# STML451RE_Buck.net
KiCad netlist of a schematic drawn in EAGLE
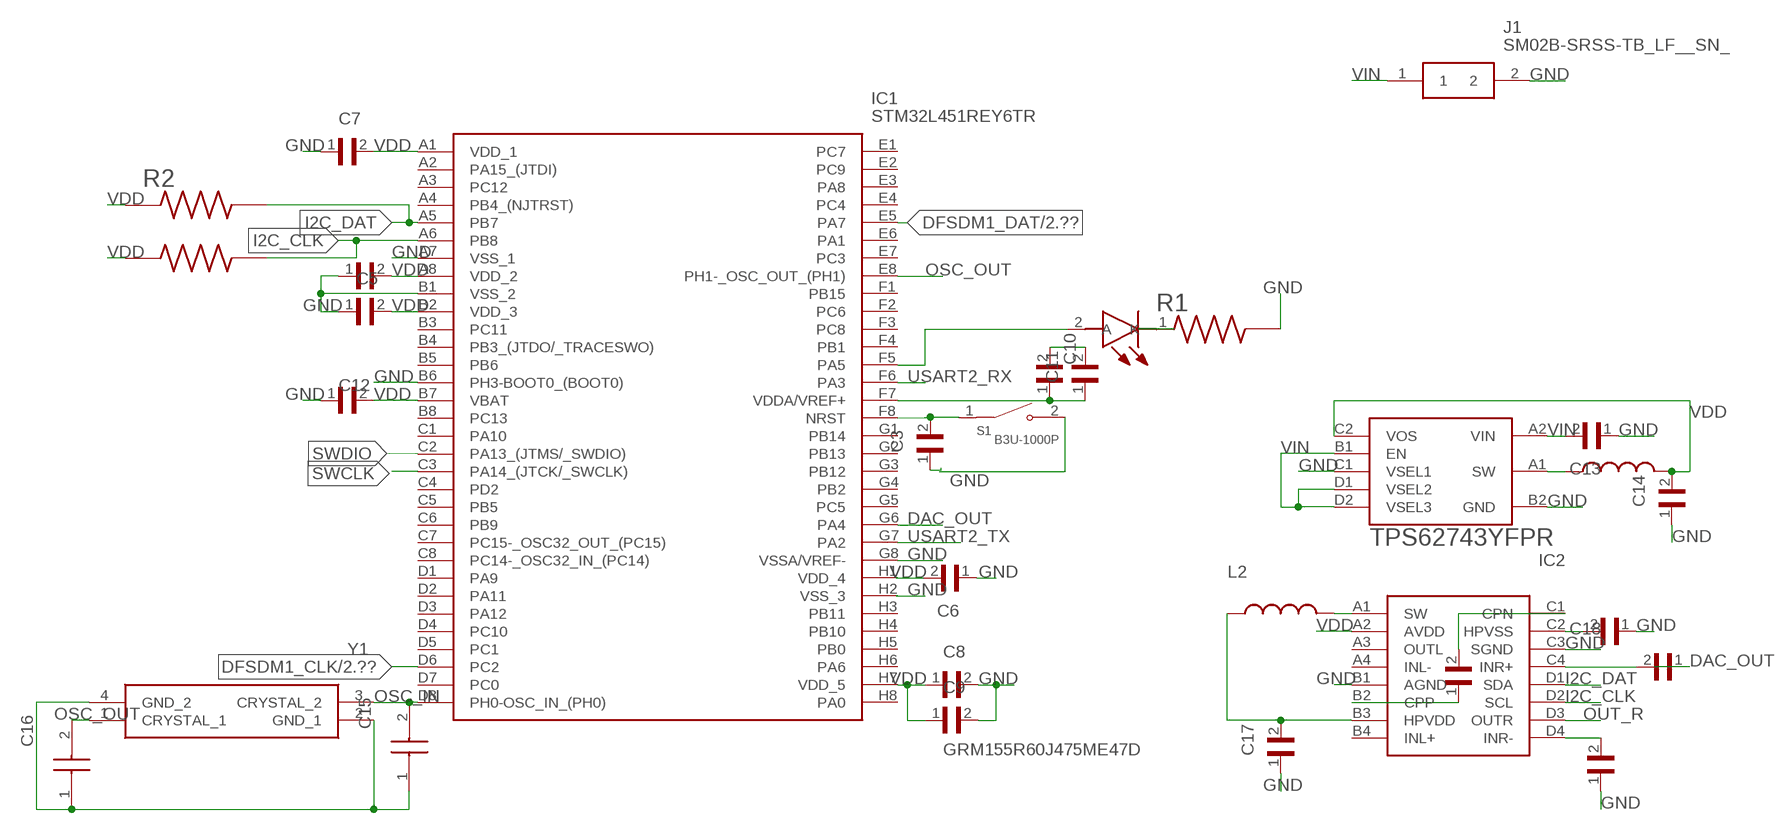
[diagram p0: schematic, sheet 1]
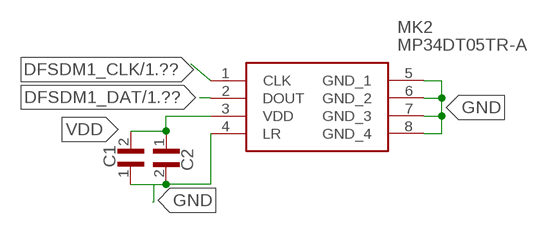
[diagram p1: schematic, sheet 2]

(export (version "E")
  (design (tool "Eeschema 10.0.6"))
  (components
    (comp (ref "C1")
      (value "GRM033C80J104KE15D")
      (footprint "eagle-import:CAPC0603X33N")
      (fields (field (name "DIGI-KEY_PART_NUMBER") "490-10390-1-ND") (field (name "MF") "Murata Electronics"))
      (libsource (lib "eagle-import") (part "GRM033C80J104KE15D"))
    )
    (comp (ref "C2")
      (value "JMK105C6105KV-F")
      (footprint "eagle-import:CAPC1005X55N")
      (fields (field (name "DIGI-KEY_PART_NUMBER") "587-3381-1-ND") (field (name "MF") "Taiyo Yuden"))
      (libsource (lib "eagle-import") (part "JMK105C6105KV-F"))
    )
    (comp (ref "MK2")
      (value "MP34DT05TR-A")
      (footprint "eagle-import:MP34DT05TRA")
      (fields (field (name "MOUSER_PART_NUMBER") "511-MP34DT05TR-A"))
      (libsource (lib "eagle-import") (part "MP34DT05TR-A"))
    )
    (comp (ref "C3")
      (value "GRM033C80J104KE15D")
      (footprint "eagle-import:CAPC0603X33N")
      (fields (field (name "DIGI-KEY_PART_NUMBER") "490-10390-1-ND") (field (name "MF") "Murata Electronics"))
      (libsource (lib "eagle-import") (part "GRM033C80J104KE15D"))
    )
    (comp (ref "C4")
      (value "GRM033C80J104KE15D")
      (footprint "eagle-import:CAPC0603X33N")
      (fields (field (name "DIGI-KEY_PART_NUMBER") "490-10390-1-ND") (field (name "MF") "Murata Electronics"))
      (libsource (lib "eagle-import") (part "GRM033C80J104KE15D"))
    )
    (comp (ref "C5")
      (value "GRM033C80J104KE15D")
      (footprint "eagle-import:CAPC0603X33N")
      (fields (field (name "DIGI-KEY_PART_NUMBER") "490-10390-1-ND") (field (name "MF") "Murata Electronics"))
      (libsource (lib "eagle-import") (part "GRM033C80J104KE15D"))
    )
    (comp (ref "C6")
      (value "GRM033C80J104KE15D")
      (footprint "eagle-import:CAPC0603X33N")
      (fields (field (name "DIGI-KEY_PART_NUMBER") "490-10390-1-ND") (field (name "MF") "Murata Electronics"))
      (libsource (lib "eagle-import") (part "GRM033C80J104KE15D"))
    )
    (comp (ref "C7")
      (value "GRM033C80J104KE15D")
      (footprint "eagle-import:CAPC0603X33N")
      (fields (field (name "DIGI-KEY_PART_NUMBER") "490-10390-1-ND") (field (name "MF") "Murata Electronics"))
      (libsource (lib "eagle-import") (part "GRM033C80J104KE15D"))
    )
    (comp (ref "C8")
      (value "GRM033C80J104KE15D")
      (footprint "eagle-import:CAPC0603X33N")
      (fields (field (name "DIGI-KEY_PART_NUMBER") "490-10390-1-ND") (field (name "MF") "Murata Electronics"))
      (libsource (lib "eagle-import") (part "GRM033C80J104KE15D"))
    )
    (comp (ref "C9")
      (value "GRM155R60J475ME47D")
      (footprint "eagle-import:CAPC1005X60N")
      (fields (field (name "DIGI-KEY_PART_NUMBER") "490-5915-1-ND") (field (name "MF") "Murata"))
      (libsource (lib "eagle-import") (part "GRM155R60J475ME47D"))
    )
    (comp (ref "C10")
      (value "GRM033C80J104KE15D")
      (footprint "eagle-import:CAPC0603X33N")
      (fields (field (name "DIGI-KEY_PART_NUMBER") "490-10390-1-ND") (field (name "MF") "Murata Electronics"))
      (libsource (lib "eagle-import") (part "GRM033C80J104KE15D"))
    )
    (comp (ref "C11")
      (value "JMK105C6105KV-F")
      (footprint "eagle-import:CAPC1005X55N")
      (fields (field (name "DIGI-KEY_PART_NUMBER") "587-3381-1-ND") (field (name "MF") "Taiyo Yuden"))
      (libsource (lib "eagle-import") (part "JMK105C6105KV-F"))
    )
    (comp (ref "C12")
      (value "GRM033C80J104KE15D")
      (footprint "eagle-import:CAPC0603X33N")
      (fields (field (name "DIGI-KEY_PART_NUMBER") "490-10390-1-ND") (field (name "MF") "Murata Electronics"))
      (libsource (lib "eagle-import") (part "GRM033C80J104KE15D"))
    )
    (comp (ref "C13")
      (value "GRM155R60J475ME47D")
      (footprint "eagle-import:CAPC1005X60N")
      (fields (field (name "DIGI-KEY_PART_NUMBER") "490-5915-1-ND") (field (name "MF") "Murata"))
      (libsource (lib "eagle-import") (part "GRM155R60J475ME47D"))
    )
    (comp (ref "C14")
      (value "GRM155R60J106ME15D")
      (footprint "eagle-import:CAPC1005X65N")
      (fields (field (name "DIGI-KEY_PART_NUMBER") "490-13238-1-ND") (field (name "MF") "Murata"))
      (libsource (lib "eagle-import") (part "GRM155R60J106ME15D"))
    )
    (comp (ref "C15")
      (value "0101YA120JAT2A")
      (footprint "eagle-import:CAPC0402X22N")
      (fields (field (name "MOUSER_PART_NUMBER") "581-0101YA120JAT2A"))
      (libsource (lib "eagle-import") (part "0101YA120JAT2A"))
    )
    (comp (ref "C16")
      (value "0101YA120JAT2A")
      (footprint "eagle-import:CAPC0402X22N")
      (fields (field (name "MOUSER_PART_NUMBER") "581-0101YA120JAT2A"))
      (libsource (lib "eagle-import") (part "0101YA120JAT2A"))
    )
    (comp (ref "C17")
      (value "GRM155R60J225KE95D")
      (footprint "eagle-import:CAPC1005X55N")
      (fields (field (name "DIGI-KEY_PART_NUMBER") "490-12532-1-ND") (field (name "MF") "Murata"))
      (libsource (lib "eagle-import") (part "GRM155R60J225KE95D"))
    )
    (comp (ref "C18")
      (value "GRM155R60J225KE95D")
      (footprint "eagle-import:CAPC1005X55N")
      (fields (field (name "DIGI-KEY_PART_NUMBER") "490-12532-1-ND") (field (name "MF") "Murata"))
      (libsource (lib "eagle-import") (part "GRM155R60J225KE95D"))
    )
    (comp (ref "C19")
      (value "JMK105C6105KV-F")
      (footprint "eagle-import:CAPC1005X55N")
      (fields (field (name "DIGI-KEY_PART_NUMBER") "587-3381-1-ND") (field (name "MF") "Taiyo Yuden"))
      (libsource (lib "eagle-import") (part "JMK105C6105KV-F"))
    )
    (comp (ref "C20")
      (value "JMK105C6105KV-F")
      (footprint "eagle-import:CAPC1005X55N")
      (fields (field (name "DIGI-KEY_PART_NUMBER") "587-3381-1-ND") (field (name "MF") "Taiyo Yuden"))
      (libsource (lib "eagle-import") (part "JMK105C6105KV-F"))
    )
    (comp (ref "C21")
      (value "JMK105C6105KV-F")
      (footprint "eagle-import:CAPC1005X55N")
      (fields (field (name "DIGI-KEY_PART_NUMBER") "587-3381-1-ND") (field (name "MF") "Taiyo Yuden"))
      (libsource (lib "eagle-import") (part "JMK105C6105KV-F"))
    )
    (comp (ref "IC1")
      (value "STM32L451REY6TR")
      (footprint "eagle-import:BGA64C40P8X8_336X366X58")
      (fields (field (name "MOUSER_PART_NUMBER") "511-STM32L451REY6TR"))
      (libsource (lib "eagle-import") (part "STM32L451REY6TR"))
    )
    (comp (ref "IC2")
      (value "TPA6140A2YFFT")
      (footprint "eagle-import:BGA16C40P4X4_156X156X63")
      (fields (field (name "MOUSER_PART_NUMBER") "595-TPA6140A2YFFT"))
      (libsource (lib "eagle-import") (part "TPA6140A2YFFT"))
    )
    (comp (ref "J1")
      (value "SM02B-SRSS-TB_LF__SN_")
      (footprint "eagle-import:SM02B-SRSS-TB")
      (fields (field (name "ARROW_PART_NUMBER") "SM02B-SRSS-TB(LF)(SN)"))
      (libsource (lib "eagle-import") (part "SM02B-SRSS-TB_LF__SN_"))
    )
    (comp (ref "L1")
      (value "1285AS-H-2R2M=P2")
      (footprint "eagle-import:INDC2016X100N")
      (fields (field (name "DIGI-KEY_PART_NUMBER") "490-10600-1-ND") (field (name "MF") "Murata Electronics"))
      (libsource (lib "eagle-import") (part "1285AS-H-2R2M=P2"))
    )
    (comp (ref "L2")
      (value "LQM21PN2R2MC0D")
      (footprint "eagle-import:INDC2012X55N")
      (fields (field (name "DIGI-KEY_PART_NUMBER") "490-4994-1-ND") (field (name "MF") "Murata"))
      (libsource (lib "eagle-import") (part "LQM21PN2R2MC0D"))
    )
    (comp (ref "LED1")
      (value "VLMS1500-GS08")
      (footprint "eagle-import:VLMG1500GS08")
      (fields (field (name "MOUSER_PART_NUMBER") "78-VLMS1500-GS08"))
      (libsource (lib "eagle-import") (part "VLMS1500-GS08"))
    )
    (comp (ref "R1")
      (value "CRCW02012K20FKED")
      (footprint "eagle-import:RESC0603X28N")
      (fields (field (name "DIGI-KEY_PART_NUMBER") "541-2.20KAABCT-ND") (field (name "MF") "Vishay"))
      (libsource (lib "eagle-import") (part "CRCW02012K20FKED"))
    )
    (comp (ref "R2")
      (value "ERA-2AEB122X")
      (footprint "eagle-import:RESC1005X40N")
      (fields (field (name "DIGI-KEY_PART_NUMBER") "P1.2KDCCT-ND") (field (name "MF") "Panasonic"))
      (libsource (lib "eagle-import") (part "ERA-2AEB122X"))
    )
    (comp (ref "R3")
      (value "ERA-2AEB122X")
      (footprint "eagle-import:RESC1005X40N")
      (fields (field (name "DIGI-KEY_PART_NUMBER") "P1.2KDCCT-ND") (field (name "MF") "Panasonic"))
      (libsource (lib "eagle-import") (part "ERA-2AEB122X"))
    )
    (comp (ref "S1")
      (value "B3U-1000P")
      (footprint "eagle-import:SW_B3U-1000P")
      (fields (field (name "DIGI-KEY_PART_NUMBER") "SW1020CT-ND") (field (name "MF") "Omron"))
      (libsource (lib "eagle-import") (part "B3U-1000P"))
    )
    (comp (ref "U1")
      (value "TPS62743YFPR")
      (footprint "eagle-import:BGA8N40P2X4_87X156X50")
      (fields (field (name "DIGI-KEY_PART_NUMBER") "296-42392-1-ND") (field (name "MF") "Texas Instruments"))
      (libsource (lib "eagle-import") (part "TPS62743YFPR"))
    )
    (comp (ref "Y1")
      (value "FL0800008Q")
      (footprint "eagle-import:FL0800008Q")
      (fields (field (name "MOUSER_PART_NUMBER") "729-FL0800008Q"))
      (libsource (lib "eagle-import") (part "FL0800008Q"))
    )
  )
  (nets
    (net (code "1") (name "DAC_OUT") (class "Default")
      (node (ref "C21") (pin "1") (pinfunction "1_1") (pintype "passive"))
      (node (ref "IC1") (pin "G6") (pinfunction "PA4_G6") (pintype "bidirectional"))
    )
    (net (code "2") (name "DFSDM1_CLK") (class "Default")
      (node (ref "IC1") (pin "D6") (pinfunction "PC2_D6") (pintype "bidirectional"))
      (node (ref "MK2") (pin "1") (pinfunction "CLK_1") (pintype "bidirectional"))
    )
    (net (code "3") (name "DFSDM1_DAT") (class "Default")
      (node (ref "IC1") (pin "E5") (pinfunction "PA7_E5") (pintype "bidirectional"))
      (node (ref "MK2") (pin "2") (pinfunction "DOUT_2") (pintype "bidirectional"))
    )
    (net (code "4") (name "GND") (class "Default")
      (node (ref "C12") (pin "1") (pinfunction "1_1") (pintype "passive"))
      (node (ref "C13") (pin "1") (pinfunction "1_1") (pintype "passive"))
      (node (ref "C14") (pin "1") (pinfunction "1_1") (pintype "passive"))
      (node (ref "C15") (pin "1") (pinfunction "1_1") (pintype "bidirectional"))
      (node (ref "C16") (pin "1") (pinfunction "1_1") (pintype "bidirectional"))
      (node (ref "C17") (pin "1") (pinfunction "1_1") (pintype "passive"))
      (node (ref "C18") (pin "1") (pinfunction "1_1") (pintype "passive"))
      (node (ref "C20") (pin "1") (pinfunction "1_1") (pintype "passive"))
      (node (ref "C3") (pin "1") (pinfunction "1_1") (pintype "passive"))
      (node (ref "C4") (pin "1") (pinfunction "1_1") (pintype "passive"))
      (node (ref "C5") (pin "1") (pinfunction "1_1") (pintype "passive"))
      (node (ref "C6") (pin "1") (pinfunction "1_1") (pintype "passive"))
      (node (ref "C7") (pin "1") (pinfunction "1_1") (pintype "passive"))
      (node (ref "C8") (pin "2") (pinfunction "2_2") (pintype "passive"))
      (node (ref "C9") (pin "2") (pinfunction "2_2") (pintype "passive"))
      (node (ref "IC1") (pin "A7") (pinfunction "VSS_1_A7") (pintype "bidirectional"))
      (node (ref "IC1") (pin "B1") (pinfunction "VSS_2_B1") (pintype "bidirectional"))
      (node (ref "IC1") (pin "B6") (pinfunction "PH3-BOOT0_(BOOT0)_B6") (pintype "bidirectional"))
      (node (ref "IC1") (pin "G8") (pinfunction "VSSA/VREF-_G8") (pintype "bidirectional"))
      (node (ref "IC1") (pin "H2") (pinfunction "VSS_3_H2") (pintype "bidirectional"))
      (node (ref "IC2") (pin "B1") (pinfunction "AGND_B1") (pintype "bidirectional"))
      (node (ref "IC2") (pin "C3") (pinfunction "SGND_C3") (pintype "bidirectional"))
      (node (ref "J1") (pin "2") (pinfunction "2_2") (pintype "bidirectional"))
      (node (ref "MK2") (pin "5") (pinfunction "GND_1_5") (pintype "bidirectional"))
      (node (ref "MK2") (pin "6") (pinfunction "GND_2_6") (pintype "bidirectional"))
      (node (ref "MK2") (pin "7") (pinfunction "GND_3_7") (pintype "bidirectional"))
      (node (ref "MK2") (pin "8") (pinfunction "GND_4_8") (pintype "bidirectional"))
      (node (ref "R1") (pin "2") (pinfunction "2_2") (pintype "passive"))
      (node (ref "U1") (pin "B2") (pinfunction "GND_B2") (pintype "passive"))
      (node (ref "U1") (pin "C1") (pinfunction "VSEL1_C1") (pintype "input"))
      (node (ref "Y1") (pin "2") (pinfunction "GND_1_2") (pintype "bidirectional"))
      (node (ref "Y1") (pin "4") (pinfunction "GND_2_4") (pintype "bidirectional"))
    )
    (net (code "5") (name "I2C_CLK") (class "Default")
      (node (ref "IC1") (pin "A6") (pinfunction "PB8_A6") (pintype "bidirectional"))
      (node (ref "IC2") (pin "D2") (pinfunction "SCL_D2") (pintype "bidirectional"))
      (node (ref "R3") (pin "2") (pinfunction "2_2") (pintype "passive"))
    )
    (net (code "6") (name "I2C_DAT") (class "Default")
      (node (ref "IC1") (pin "A5") (pinfunction "PB7_A5") (pintype "bidirectional"))
      (node (ref "IC2") (pin "D1") (pinfunction "SDA_D1") (pintype "bidirectional"))
      (node (ref "R2") (pin "2") (pinfunction "2_2") (pintype "passive"))
    )
    (net (code "7") (name "Net-(C3-Pad2)") (class "Default")
      (node (ref "C3") (pin "2") (pinfunction "2_2") (pintype "passive"))
      (node (ref "S1") (pin "1") (pinfunction "1_1") (pintype "passive"))
    )
    (net (code "8") (name "Net-(C10-Pad2)") (class "Default")
      (node (ref "C10") (pin "2") (pinfunction "2_2") (pintype "passive"))
      (node (ref "C11") (pin "2") (pinfunction "2_2") (pintype "passive"))
    )
    (net (code "9") (name "Net-(IC1-PA5)") (class "Default")
      (node (ref "IC1") (pin "F5") (pinfunction "PA5_F5") (pintype "bidirectional"))
      (node (ref "LED1") (pin "2") (pinfunction "A_2") (pintype "bidirectional"))
    )
    (net (code "10") (name "Net-(IC1-VDDA{slash}VREF+)") (class "Default")
      (node (ref "C10") (pin "1") (pinfunction "1_1") (pintype "passive"))
      (node (ref "C11") (pin "1") (pinfunction "1_1") (pintype "passive"))
      (node (ref "IC1") (pin "F7") (pinfunction "VDDA/VREF+_F7") (pintype "bidirectional"))
    )
    (net (code "11") (name "Net-(IC2-CPN)") (class "Default")
      (node (ref "C19") (pin "2") (pinfunction "2_2") (pintype "passive"))
      (node (ref "IC2") (pin "C1") (pinfunction "CPN_C1") (pintype "bidirectional"))
    )
    (net (code "12") (name "Net-(IC2-CPP)") (class "Default")
      (node (ref "C19") (pin "1") (pinfunction "1_1") (pintype "passive"))
      (node (ref "IC2") (pin "B2") (pinfunction "CPP_B2") (pintype "bidirectional"))
    )
    (net (code "13") (name "Net-(IC2-HPVDD)") (class "Default")
      (node (ref "C17") (pin "2") (pinfunction "2_2") (pintype "passive"))
      (node (ref "IC2") (pin "B3") (pinfunction "HPVDD_B3") (pintype "bidirectional"))
      (node (ref "L2") (pin "1") (pinfunction "1_1") (pintype "passive"))
    )
    (net (code "14") (name "Net-(IC2-HPVSS)") (class "Default")
      (node (ref "C18") (pin "2") (pinfunction "2_2") (pintype "passive"))
      (node (ref "IC2") (pin "C2") (pinfunction "HPVSS_C2") (pintype "bidirectional"))
    )
    (net (code "15") (name "Net-(IC2-INR+)") (class "Default")
      (node (ref "C21") (pin "2") (pinfunction "2_2") (pintype "passive"))
      (node (ref "IC2") (pin "C4") (pinfunction "INR+_C4") (pintype "bidirectional"))
    )
    (net (code "16") (name "Net-(IC2-INR-)") (class "Default")
      (node (ref "C20") (pin "2") (pinfunction "2_2") (pintype "passive"))
      (node (ref "IC2") (pin "D4") (pinfunction "INR-_D4") (pintype "bidirectional"))
    )
    (net (code "17") (name "Net-(IC2-SW)") (class "Default")
      (node (ref "IC2") (pin "A1") (pinfunction "SW_A1") (pintype "bidirectional"))
      (node (ref "L2") (pin "2") (pinfunction "2_2") (pintype "passive"))
    )
    (net (code "18") (name "Net-(LED1-K)") (class "Default")
      (node (ref "LED1") (pin "1") (pinfunction "K_1") (pintype "bidirectional"))
      (node (ref "R1") (pin "1") (pinfunction "1_1") (pintype "passive"))
    )
    (net (code "19") (name "Net-(MK2-LR)") (class "Default")
      (node (ref "C1") (pin "1") (pinfunction "1_1") (pintype "passive"))
      (node (ref "C2") (pin "2") (pinfunction "2_2") (pintype "passive"))
      (node (ref "MK2") (pin "4") (pinfunction "LR_4") (pintype "bidirectional"))
    )
    (net (code "20") (name "Net-(U1-SW)") (class "Default")
      (node (ref "L1") (pin "1") (pinfunction "1_1") (pintype "passive"))
      (node (ref "U1") (pin "A1") (pinfunction "SW_A1") (pintype "output"))
    )
    (net (code "21") (name "OSC_IN") (class "Default")
      (node (ref "C15") (pin "2") (pinfunction "2_2") (pintype "bidirectional"))
      (node (ref "IC1") (pin "D8") (pinfunction "PH0-OSC_IN_(PH0)_D8") (pintype "bidirectional"))
      (node (ref "Y1") (pin "3") (pinfunction "CRYSTAL_2_3") (pintype "bidirectional"))
    )
    (net (code "22") (name "OSC_OUT") (class "Default")
      (node (ref "C16") (pin "2") (pinfunction "2_2") (pintype "bidirectional"))
      (node (ref "IC1") (pin "E8") (pinfunction "PH1-_OSC_OUT_(PH1)_E8") (pintype "bidirectional"))
      (node (ref "Y1") (pin "1") (pinfunction "CRYSTAL_1_1") (pintype "bidirectional"))
    )
    (net (code "23") (name "OUT_R") (class "Default")
      (node (ref "IC2") (pin "D3") (pinfunction "OUTR_D3") (pintype "bidirectional"))
    )
    (net (code "24") (name "SWCLK") (class "Default")
      (node (ref "IC1") (pin "C3") (pinfunction "PA14_(JTCK/_SWCLK)_C3") (pintype "bidirectional"))
    )
    (net (code "25") (name "SWDIO") (class "Default")
      (node (ref "IC1") (pin "C2") (pinfunction "PA13_(JTMS/_SWDIO)_C2") (pintype "bidirectional"))
    )
    (net (code "26") (name "USART2_RX") (class "Default")
      (node (ref "IC1") (pin "F6") (pinfunction "PA3_F6") (pintype "bidirectional"))
    )
    (net (code "27") (name "USART2_TX") (class "Default")
      (node (ref "IC1") (pin "G7") (pinfunction "PA2_G7") (pintype "bidirectional"))
    )
    (net (code "28") (name "VDD") (class "Default")
      (node (ref "C1") (pin "2") (pinfunction "2_2") (pintype "passive"))
      (node (ref "C12") (pin "2") (pinfunction "2_2") (pintype "passive"))
      (node (ref "C14") (pin "2") (pinfunction "2_2") (pintype "passive"))
      (node (ref "C2") (pin "1") (pinfunction "1_1") (pintype "passive"))
      (node (ref "C4") (pin "2") (pinfunction "2_2") (pintype "passive"))
      (node (ref "C5") (pin "2") (pinfunction "2_2") (pintype "passive"))
      (node (ref "C6") (pin "2") (pinfunction "2_2") (pintype "passive"))
      (node (ref "C7") (pin "2") (pinfunction "2_2") (pintype "passive"))
      (node (ref "C8") (pin "1") (pinfunction "1_1") (pintype "passive"))
      (node (ref "C9") (pin "1") (pinfunction "1_1") (pintype "passive"))
      (node (ref "IC1") (pin "A1") (pinfunction "VDD_1_A1") (pintype "bidirectional"))
      (node (ref "IC1") (pin "A8") (pinfunction "VDD_2_A8") (pintype "bidirectional"))
      (node (ref "IC1") (pin "B2") (pinfunction "VDD_3_B2") (pintype "bidirectional"))
      (node (ref "IC1") (pin "B7") (pinfunction "VBAT_B7") (pintype "bidirectional"))
      (node (ref "IC1") (pin "H1") (pinfunction "VDD_4_H1") (pintype "bidirectional"))
      (node (ref "IC1") (pin "H7") (pinfunction "VDD_5_H7") (pintype "bidirectional"))
      (node (ref "IC2") (pin "A2") (pinfunction "AVDD_A2") (pintype "bidirectional"))
      (node (ref "L1") (pin "2") (pinfunction "2_2") (pintype "passive"))
      (node (ref "MK2") (pin "3") (pinfunction "VDD_3") (pintype "bidirectional"))
      (node (ref "R2") (pin "1") (pinfunction "1_1") (pintype "passive"))
      (node (ref "R3") (pin "1") (pinfunction "1_1") (pintype "passive"))
      (node (ref "U1") (pin "C2") (pinfunction "VOS_C2") (pintype "input"))
    )
    (net (code "29") (name "VIN") (class "Default")
      (node (ref "C13") (pin "2") (pinfunction "2_2") (pintype "passive"))
      (node (ref "J1") (pin "1") (pinfunction "1_1") (pintype "bidirectional"))
      (node (ref "U1") (pin "A2") (pinfunction "VIN_A2") (pintype "power_in"))
      (node (ref "U1") (pin "B1") (pinfunction "EN_B1") (pintype "input"))
      (node (ref "U1") (pin "D1") (pinfunction "VSEL2_D1") (pintype "input"))
      (node (ref "U1") (pin "D2") (pinfunction "VSEL3_D2") (pintype "input"))
    )
    (net (code "30") (name "unconnected-(IC1-NRST-PadF8)") (class "Default")
      (node (ref "IC1") (pin "F8") (pinfunction "NRST_F8") (pintype "bidirectional"))
    )
    (net (code "31") (name "unconnected-(IC1-PA0-PadH8)") (class "Default")
      (node (ref "IC1") (pin "H8") (pinfunction "PA0_H8") (pintype "bidirectional"))
    )
    (net (code "32") (name "unconnected-(IC1-PA1-PadE6)") (class "Default")
      (node (ref "IC1") (pin "E6") (pinfunction "PA1_E6") (pintype "bidirectional"))
    )
    (net (code "33") (name "unconnected-(IC1-PA6-PadH6)") (class "Default")
      (node (ref "IC1") (pin "H6") (pinfunction "PA6_H6") (pintype "bidirectional"))
    )
    (net (code "34") (name "unconnected-(IC1-PA8-PadE3)") (class "Default")
      (node (ref "IC1") (pin "E3") (pinfunction "PA8_E3") (pintype "bidirectional"))
    )
    (net (code "35") (name "unconnected-(IC1-PA9-PadD1)") (class "Default")
      (node (ref "IC1") (pin "D1") (pinfunction "PA9_D1") (pintype "bidirectional"))
    )
    (net (code "36") (name "unconnected-(IC1-PA10-PadC1)") (class "Default")
      (node (ref "IC1") (pin "C1") (pinfunction "PA10_C1") (pintype "bidirectional"))
    )
    (net (code "37") (name "unconnected-(IC1-PA11-PadD2)") (class "Default")
      (node (ref "IC1") (pin "D2") (pinfunction "PA11_D2") (pintype "bidirectional"))
    )
    (net (code "38") (name "unconnected-(IC1-PA12-PadD3)") (class "Default")
      (node (ref "IC1") (pin "D3") (pinfunction "PA12_D3") (pintype "bidirectional"))
    )
    (net (code "39") (name "unconnected-(IC1-PA15_(JTDI)-PadA2)") (class "Default")
      (node (ref "IC1") (pin "A2") (pinfunction "PA15_(JTDI)_A2") (pintype "bidirectional"))
    )
    (net (code "40") (name "unconnected-(IC1-PB0-PadH5)") (class "Default")
      (node (ref "IC1") (pin "H5") (pinfunction "PB0_H5") (pintype "bidirectional"))
    )
    (net (code "41") (name "unconnected-(IC1-PB1-PadF4)") (class "Default")
      (node (ref "IC1") (pin "F4") (pinfunction "PB1_F4") (pintype "bidirectional"))
    )
    (net (code "42") (name "unconnected-(IC1-PB2-PadG4)") (class "Default")
      (node (ref "IC1") (pin "G4") (pinfunction "PB2_G4") (pintype "bidirectional"))
    )
    (net (code "43") (name "unconnected-(IC1-PB3_(JTDO{slash}_TRACESWO)-PadB4)") (class "Default")
      (node (ref "IC1") (pin "B4") (pinfunction "PB3_(JTDO/_TRACESWO)_B4") (pintype "bidirectional"))
    )
    (net (code "44") (name "unconnected-(IC1-PB4_(NJTRST)-PadA4)") (class "Default")
      (node (ref "IC1") (pin "A4") (pinfunction "PB4_(NJTRST)_A4") (pintype "bidirectional"))
    )
    (net (code "45") (name "unconnected-(IC1-PB5-PadC5)") (class "Default")
      (node (ref "IC1") (pin "C5") (pinfunction "PB5_C5") (pintype "bidirectional"))
    )
    (net (code "46") (name "unconnected-(IC1-PB6-PadB5)") (class "Default")
      (node (ref "IC1") (pin "B5") (pinfunction "PB6_B5") (pintype "bidirectional"))
    )
    (net (code "47") (name "unconnected-(IC1-PB9-PadC6)") (class "Default")
      (node (ref "IC1") (pin "C6") (pinfunction "PB9_C6") (pintype "bidirectional"))
    )
    (net (code "48") (name "unconnected-(IC1-PB10-PadH4)") (class "Default")
      (node (ref "IC1") (pin "H4") (pinfunction "PB10_H4") (pintype "bidirectional"))
    )
    (net (code "49") (name "unconnected-(IC1-PB11-PadH3)") (class "Default")
      (node (ref "IC1") (pin "H3") (pinfunction "PB11_H3") (pintype "bidirectional"))
    )
    (net (code "50") (name "unconnected-(IC1-PB12-PadG3)") (class "Default")
      (node (ref "IC1") (pin "G3") (pinfunction "PB12_G3") (pintype "bidirectional"))
    )
    (net (code "51") (name "unconnected-(IC1-PB13-PadG2)") (class "Default")
      (node (ref "IC1") (pin "G2") (pinfunction "PB13_G2") (pintype "bidirectional"))
    )
    (net (code "52") (name "unconnected-(IC1-PB14-PadG1)") (class "Default")
      (node (ref "IC1") (pin "G1") (pinfunction "PB14_G1") (pintype "bidirectional"))
    )
    (net (code "53") (name "unconnected-(IC1-PB15-PadF1)") (class "Default")
      (node (ref "IC1") (pin "F1") (pinfunction "PB15_F1") (pintype "bidirectional"))
    )
    (net (code "54") (name "unconnected-(IC1-PC0-PadD7)") (class "Default")
      (node (ref "IC1") (pin "D7") (pinfunction "PC0_D7") (pintype "bidirectional"))
    )
    (net (code "55") (name "unconnected-(IC1-PC1-PadD5)") (class "Default")
      (node (ref "IC1") (pin "D5") (pinfunction "PC1_D5") (pintype "bidirectional"))
    )
    (net (code "56") (name "unconnected-(IC1-PC3-PadE7)") (class "Default")
      (node (ref "IC1") (pin "E7") (pinfunction "PC3_E7") (pintype "bidirectional"))
    )
    (net (code "57") (name "unconnected-(IC1-PC4-PadE4)") (class "Default")
      (node (ref "IC1") (pin "E4") (pinfunction "PC4_E4") (pintype "bidirectional"))
    )
    (net (code "58") (name "unconnected-(IC1-PC5-PadG5)") (class "Default")
      (node (ref "IC1") (pin "G5") (pinfunction "PC5_G5") (pintype "bidirectional"))
    )
    (net (code "59") (name "unconnected-(IC1-PC6-PadF2)") (class "Default")
      (node (ref "IC1") (pin "F2") (pinfunction "PC6_F2") (pintype "bidirectional"))
    )
    (net (code "60") (name "unconnected-(IC1-PC7-PadE1)") (class "Default")
      (node (ref "IC1") (pin "E1") (pinfunction "PC7_E1") (pintype "bidirectional"))
    )
    (net (code "61") (name "unconnected-(IC1-PC8-PadF3)") (class "Default")
      (node (ref "IC1") (pin "F3") (pinfunction "PC8_F3") (pintype "bidirectional"))
    )
    (net (code "62") (name "unconnected-(IC1-PC9-PadE2)") (class "Default")
      (node (ref "IC1") (pin "E2") (pinfunction "PC9_E2") (pintype "bidirectional"))
    )
    (net (code "63") (name "unconnected-(IC1-PC10-PadD4)") (class "Default")
      (node (ref "IC1") (pin "D4") (pinfunction "PC10_D4") (pintype "bidirectional"))
    )
    (net (code "64") (name "unconnected-(IC1-PC11-PadB3)") (class "Default")
      (node (ref "IC1") (pin "B3") (pinfunction "PC11_B3") (pintype "bidirectional"))
    )
    (net (code "65") (name "unconnected-(IC1-PC12-PadA3)") (class "Default")
      (node (ref "IC1") (pin "A3") (pinfunction "PC12_A3") (pintype "bidirectional"))
    )
    (net (code "66") (name "unconnected-(IC1-PC13-PadB8)") (class "Default")
      (node (ref "IC1") (pin "B8") (pinfunction "PC13_B8") (pintype "bidirectional"))
    )
    (net (code "67") (name "unconnected-(IC1-PC14-_OSC32_IN_(PC14)-PadC8)") (class "Default")
      (node (ref "IC1") (pin "C8") (pinfunction "PC14-_OSC32_IN_(PC14)_C8") (pintype "bidirectional"))
    )
    (net (code "68") (name "unconnected-(IC1-PC15-_OSC32_OUT_(PC15)-PadC7)") (class "Default")
      (node (ref "IC1") (pin "C7") (pinfunction "PC15-_OSC32_OUT_(PC15)_C7") (pintype "bidirectional"))
    )
    (net (code "69") (name "unconnected-(IC1-PD2-PadC4)") (class "Default")
      (node (ref "IC1") (pin "C4") (pinfunction "PD2_C4") (pintype "bidirectional"))
    )
    (net (code "70") (name "unconnected-(IC2-INL+-PadB4)") (class "Default")
      (node (ref "IC2") (pin "B4") (pinfunction "INL+_B4") (pintype "bidirectional"))
    )
    (net (code "71") (name "unconnected-(IC2-INL--PadA4)") (class "Default")
      (node (ref "IC2") (pin "A4") (pinfunction "INL-_A4") (pintype "bidirectional"))
    )
    (net (code "72") (name "unconnected-(IC2-OUTL-PadA3)") (class "Default")
      (node (ref "IC2") (pin "A3") (pinfunction "OUTL_A3") (pintype "bidirectional"))
    )
    (net (code "73") (name "unconnected-(S1-Pad2)") (class "Default")
      (node (ref "S1") (pin "2") (pinfunction "2_2") (pintype "passive"))
    )
  )
)
